# USB.net
KiCad netlist of a schematic drawn in Altium Designer
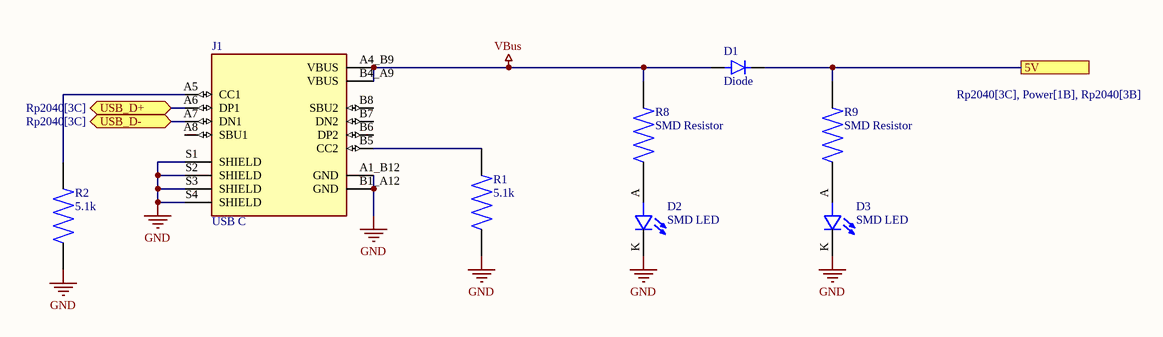
[diagram p0: USB.SchDoc]

(export (version "E")
  (design (tool "Eeschema 10.0.6"))
  (components
    (comp (ref "D1") (value "Diode") (footprint "Diode") (libsource (lib "Basic") (part "Diode")))
    (comp (ref "D2") (value "SMD LED") (footprint "SMD LED") (libsource (lib "Basic") (part "SMD LED")))
    (comp (ref "D3") (value "SMD LED") (footprint "SMD LED") (libsource (lib "Basic") (part "SMD LED")))
    (comp (ref "J1") (value "USB C") (footprint "USB C") (libsource (lib "Basic") (part "USB C")))
    (comp (ref "R1")
      (value "5.1k")
      (footprint "SMD Resistor")
      (libsource (lib "Basic") (part "SMD Resistor"))
    )
    (comp (ref "R2")
      (value "5.1k")
      (footprint "SMD Resistor")
      (libsource (lib "Basic") (part "SMD Resistor"))
    )
    (comp (ref "R8")
      (value "SMD Resistor")
      (footprint "SMD Resistor")
      (libsource (lib "Basic") (part "SMD Resistor"))
    )
    (comp (ref "R9")
      (value "SMD Resistor")
      (footprint "SMD Resistor")
      (libsource (lib "Basic") (part "SMD Resistor"))
    )
  )
  (nets
    (net (code "1") (name "/5V") (class "Default")
      (node (ref "D1") (pin "K") (pinfunction "K_K") (pintype "passive"))
      (node (ref "R9") (pin "1") (pinfunction "1_1") (pintype "passive"))
    )
    (net (code "2") (name "/USB_D+") (class "Default")
      (node (ref "J1") (pin "A6") (pinfunction "DP1_A6") (pintype "bidirectional"))
    )
    (net (code "3") (name "/USB_D-") (class "Default")
      (node (ref "J1") (pin "A7") (pinfunction "DN1_A7") (pintype "bidirectional"))
    )
    (net (code "4") (name "GND") (class "Default")
      (node (ref "D2") (pin "K") (pinfunction "C_K") (pintype "passive"))
      (node (ref "D3") (pin "K") (pinfunction "C_K") (pintype "passive"))
      (node (ref "J1") (pin "A1_B12") (pinfunction "GND_A1_B12") (pintype "power_in"))
      (node (ref "J1") (pin "B1_A12") (pinfunction "GND_B1_A12") (pintype "power_in"))
      (node (ref "J1") (pin "S1") (pinfunction "SHIELD_S1") (pintype "passive"))
      (node (ref "J1") (pin "S2") (pinfunction "SHIELD_S2") (pintype "passive"))
      (node (ref "J1") (pin "S3") (pinfunction "SHIELD_S3") (pintype "passive"))
      (node (ref "J1") (pin "S4") (pinfunction "SHIELD_S4") (pintype "passive"))
      (node (ref "R1") (pin "2") (pinfunction "2_2") (pintype "passive"))
      (node (ref "R2") (pin "2") (pinfunction "2_2") (pintype "passive"))
    )
    (net (code "5") (name "Net-(D2-PadA)") (class "Default")
      (node (ref "D2") (pin "A") (pinfunction "A_A") (pintype "passive"))
      (node (ref "R8") (pin "2") (pinfunction "2_2") (pintype "passive"))
    )
    (net (code "6") (name "Net-(D3-PadA)") (class "Default")
      (node (ref "D3") (pin "A") (pinfunction "A_A") (pintype "passive"))
      (node (ref "R9") (pin "2") (pinfunction "2_2") (pintype "passive"))
    )
    (net (code "7") (name "Net-(J1-CC1)") (class "Default")
      (node (ref "J1") (pin "A5") (pinfunction "CC1_A5") (pintype "bidirectional"))
      (node (ref "R2") (pin "1") (pinfunction "1_1") (pintype "passive"))
    )
    (net (code "8") (name "Net-(J1-CC2)") (class "Default")
      (node (ref "J1") (pin "B5") (pinfunction "CC2_B5") (pintype "bidirectional"))
      (node (ref "R1") (pin "1") (pinfunction "1_1") (pintype "passive"))
    )
    (net (code "9") (name "VBus") (class "Default")
      (node (ref "D1") (pin "A") (pinfunction "A_A") (pintype "passive"))
      (node (ref "J1") (pin "A4_B9") (pinfunction "VBUS_A4_B9") (pintype "power_in"))
      (node (ref "J1") (pin "B4_A9") (pinfunction "VBUS_B4_A9") (pintype "power_in"))
      (node (ref "R8") (pin "1") (pinfunction "1_1") (pintype "passive"))
    )
    (net (code "10") (name "unconnected-(J1-DN2-PadB7)") (class "Default")
      (node (ref "J1") (pin "B7") (pinfunction "DN2_B7") (pintype "bidirectional"))
    )
    (net (code "11") (name "unconnected-(J1-DP2-PadB6)") (class "Default")
      (node (ref "J1") (pin "B6") (pinfunction "DP2_B6") (pintype "bidirectional"))
    )
    (net (code "12") (name "unconnected-(J1-SBU1-PadA8)") (class "Default")
      (node (ref "J1") (pin "A8") (pinfunction "SBU1_A8") (pintype "bidirectional"))
    )
    (net (code "13") (name "unconnected-(J1-SBU2-PadB8)") (class "Default")
      (node (ref "J1") (pin "B8") (pinfunction "SBU2_B8") (pintype "bidirectional"))
    )
  )
)
